# hackgt6-badge-prototype.net
KiCad netlist of a schematic drawn in EAGLE
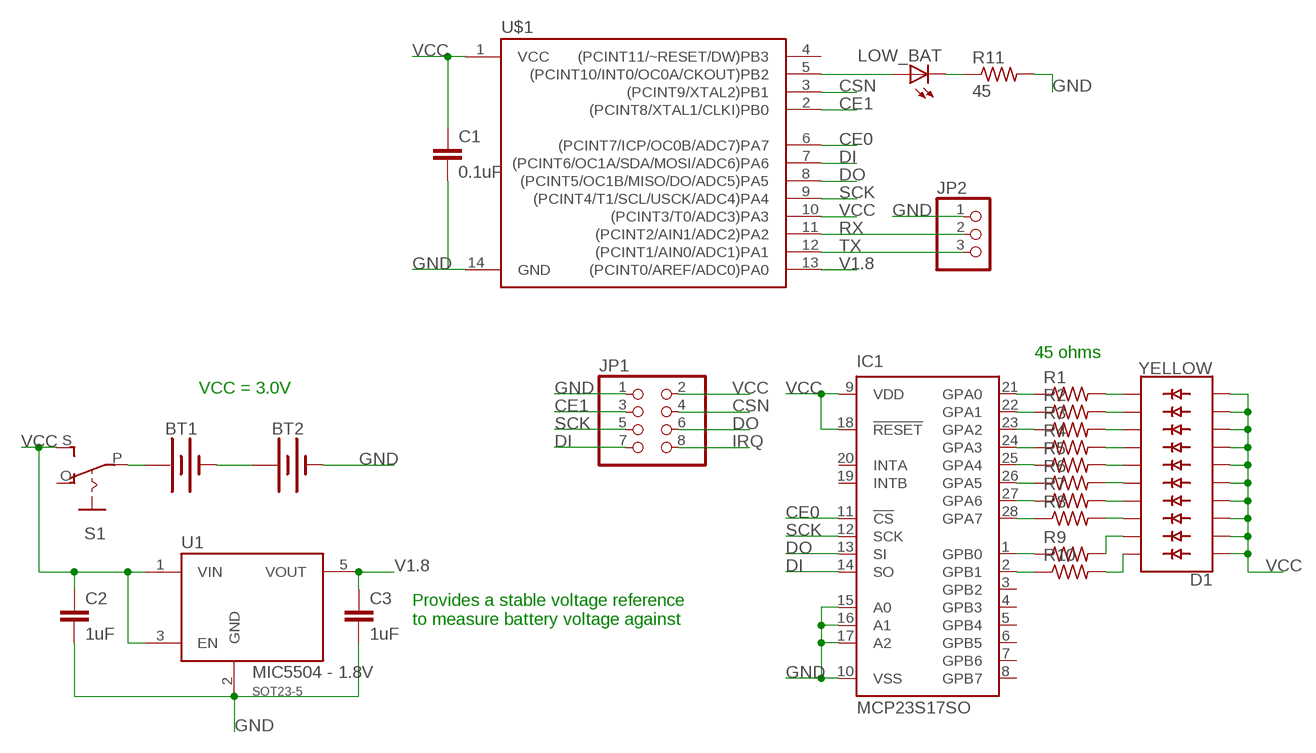
[diagram p0: schematic, sheet 1]

(export (version "E")
  (design (tool "Eeschema 10.0.6"))
  (components
    (comp (ref "BT1")
      (value "BATTERY-AA-SMD")
      (footprint "eagle-import:BATTERY-AA-SMD")
      (libsource (lib "eagle-import") (part "BATTERY-AA-SMD"))
    )
    (comp (ref "BT2")
      (value "BATTERY-AA-SMD")
      (footprint "eagle-import:BATTERY-AA-SMD")
      (libsource (lib "eagle-import") (part "BATTERY-AA-SMD"))
    )
    (comp (ref "C1")
      (value "0.1uF")
      (footprint "eagle-import:C1206")
      (libsource (lib "eagle-import") (part "C-EUC1206"))
    )
    (comp (ref "C2")
      (value "1uF")
      (footprint "eagle-import:C1206")
      (libsource (lib "eagle-import") (part "C-EUC1206"))
    )
    (comp (ref "C3")
      (value "1uF")
      (footprint "eagle-import:C1206")
      (libsource (lib "eagle-import") (part "C-EUC1206"))
    )
    (comp (ref "D1")
      (value "YELLOW")
      (footprint "eagle-import:LED_BARGRAPH_10")
      (libsource (lib "eagle-import") (part "LED_BARGRAPH_10YELLOW"))
    )
    (comp (ref "IC1")
      (value "MCP23S17SO")
      (footprint "eagle-import:SO28W")
      (fields (field (name "MF") "MICROCHIP") (field (name "MPN") "MCP23S17-E/SO"))
      (libsource (lib "eagle-import") (part "MCP23S17SO"))
    )
    (comp (ref "JP1")
      (value "PINHD-2X4/90")
      (footprint "eagle-import:2X04_90")
      (libsource (lib "eagle-import") (part "PINHD-2X4/90"))
    )
    (comp (ref "JP2")
      (value "PINHD-1X3")
      (footprint "eagle-import:1X03")
      (libsource (lib "eagle-import") (part "PINHD-1X3"))
    )
    (comp (ref "LOW_BAT")
      (value "LEDCHIPLED_1206")
      (footprint "eagle-import:CHIPLED_1206")
      (libsource (lib "eagle-import") (part "LEDCHIPLED_1206"))
    )
    (comp (ref "R1")
      (value "R-US_R1206")
      (footprint "eagle-import:R1206")
      (libsource (lib "eagle-import") (part "R-US_R1206"))
    )
    (comp (ref "R2")
      (value "R-US_R1206")
      (footprint "eagle-import:R1206")
      (libsource (lib "eagle-import") (part "R-US_R1206"))
    )
    (comp (ref "R3")
      (value "R-US_R1206")
      (footprint "eagle-import:R1206")
      (libsource (lib "eagle-import") (part "R-US_R1206"))
    )
    (comp (ref "R4")
      (value "R-US_R1206")
      (footprint "eagle-import:R1206")
      (libsource (lib "eagle-import") (part "R-US_R1206"))
    )
    (comp (ref "R5")
      (value "R-US_R1206")
      (footprint "eagle-import:R1206")
      (libsource (lib "eagle-import") (part "R-US_R1206"))
    )
    (comp (ref "R6")
      (value "R-US_R1206")
      (footprint "eagle-import:R1206")
      (libsource (lib "eagle-import") (part "R-US_R1206"))
    )
    (comp (ref "R7")
      (value "R-US_R1206")
      (footprint "eagle-import:R1206")
      (libsource (lib "eagle-import") (part "R-US_R1206"))
    )
    (comp (ref "R8")
      (value "R-US_R1206")
      (footprint "eagle-import:R1206")
      (libsource (lib "eagle-import") (part "R-US_R1206"))
    )
    (comp (ref "R9")
      (value "R-US_R1206")
      (footprint "eagle-import:R1206")
      (libsource (lib "eagle-import") (part "R-US_R1206"))
    )
    (comp (ref "R10")
      (value "R-US_R1206")
      (footprint "eagle-import:R1206")
      (libsource (lib "eagle-import") (part "R-US_R1206"))
    )
    (comp (ref "R11")
      (value "45")
      (footprint "eagle-import:R1206")
      (libsource (lib "eagle-import") (part "R-US_R1206"))
    )
    (comp (ref "S1")
      (value "EG1218S")
      (footprint "eagle-import:EG1218")
      (libsource (lib "eagle-import") (part "EG1218S"))
    )
    (comp (ref "U$1")
      (value "ATTINY84ATTINY84-20PU")
      (footprint "eagle-import:DIP14")
      (libsource (lib "eagle-import") (part "ATTINY84ATTINY84-20PU"))
    )
    (comp (ref "U1")
      (value "MIC5504 - 1.8V")
      (footprint "eagle-import:SOT23-5-DBV")
      (fields (field (name "PACKAGE") "SOT23-5"))
      (libsource (lib "eagle-import") (part "MIC550X-YM5"))
    )
  )
  (nets
    (net (code "1") (name "/CE0") (class "Default")
      (node (ref "IC1") (pin "11") (pinfunction "~{CS}_11") (pintype "input"))
      (node (ref "U$1") (pin "6") (pinfunction "(PCINT7/ICP/OC0B/ADC7)PA7_6") (pintype "bidirectional"))
    )
    (net (code "2") (name "/CE1") (class "Default")
      (node (ref "JP1") (pin "3") (pinfunction "3_3") (pintype "passive"))
      (node (ref "U$1") (pin "2") (pinfunction "(PCINT8/XTAL1/CLKI)PB0_2") (pintype "bidirectional"))
    )
    (net (code "3") (name "/CSN") (class "Default")
      (node (ref "JP1") (pin "4") (pinfunction "4_4") (pintype "passive"))
      (node (ref "U$1") (pin "3") (pinfunction "(PCINT9/XTAL2)PB1_3") (pintype "bidirectional"))
    )
    (net (code "4") (name "/DI") (class "Default")
      (node (ref "IC1") (pin "14") (pinfunction "SO_14") (pintype "output"))
      (node (ref "JP1") (pin "7") (pinfunction "7_7") (pintype "passive"))
      (node (ref "U$1") (pin "7") (pinfunction "(PCINT6/OC1A/SDA/MOSI/ADC6)PA6_7") (pintype "bidirectional"))
    )
    (net (code "5") (name "/DO") (class "Default")
      (node (ref "IC1") (pin "13") (pinfunction "SI_13") (pintype "input"))
      (node (ref "JP1") (pin "6") (pinfunction "6_6") (pintype "passive"))
      (node (ref "U$1") (pin "8") (pinfunction "(PCINT5/OC1B/MISO/DO/ADC5)PA5_8") (pintype "bidirectional"))
    )
    (net (code "6") (name "/GND") (class "Default")
      (node (ref "BT2") (pin "P$2") (pinfunction "-_P$2") (pintype "power_in"))
      (node (ref "BT2") (pin "P$4") (pinfunction "-_P$4") (pintype "power_in"))
      (node (ref "C1") (pin "2") (pinfunction "2_2") (pintype "passive"))
      (node (ref "C2") (pin "2") (pinfunction "2_2") (pintype "passive"))
      (node (ref "C3") (pin "2") (pinfunction "2_2") (pintype "passive"))
      (node (ref "IC1") (pin "10") (pinfunction "VSS_10") (pintype "power_in"))
      (node (ref "IC1") (pin "15") (pinfunction "A0_15") (pintype "input"))
      (node (ref "IC1") (pin "16") (pinfunction "A1_16") (pintype "input"))
      (node (ref "IC1") (pin "17") (pinfunction "A2_17") (pintype "input"))
      (node (ref "JP1") (pin "1") (pinfunction "1_1") (pintype "passive"))
      (node (ref "JP2") (pin "1") (pinfunction "1_1") (pintype "passive"))
      (node (ref "R11") (pin "2") (pinfunction "2_2") (pintype "passive"))
      (node (ref "U$1") (pin "14") (pinfunction "GND_14") (pintype "bidirectional"))
      (node (ref "U1") (pin "2") (pinfunction "GND_2") (pintype "bidirectional"))
    )
    (net (code "7") (name "/IRQ") (class "Default")
      (node (ref "JP1") (pin "8") (pinfunction "8_8") (pintype "passive"))
    )
    (net (code "8") (name "/RX") (class "Default")
      (node (ref "JP2") (pin "2") (pinfunction "2_2") (pintype "passive"))
      (node (ref "U$1") (pin "11") (pinfunction "(PCINT2/AIN1/ADC2)PA2_11") (pintype "bidirectional"))
    )
    (net (code "9") (name "/SCK") (class "Default")
      (node (ref "IC1") (pin "12") (pinfunction "SCK_12") (pintype "input"))
      (node (ref "JP1") (pin "5") (pinfunction "5_5") (pintype "passive"))
      (node (ref "U$1") (pin "9") (pinfunction "(PCINT4/T1/SCL/USCK/ADC4)PA4_9") (pintype "bidirectional"))
    )
    (net (code "10") (name "/TX") (class "Default")
      (node (ref "JP2") (pin "3") (pinfunction "3_3") (pintype "passive"))
      (node (ref "U$1") (pin "12") (pinfunction "(PCINT1/AIN0/ADC1)PA1_12") (pintype "bidirectional"))
    )
    (net (code "11") (name "/V1.8") (class "Default")
      (node (ref "C3") (pin "1") (pinfunction "1_1") (pintype "passive"))
      (node (ref "U$1") (pin "13") (pinfunction "(PCINT0/AREF/ADC0)PA0_13") (pintype "bidirectional"))
      (node (ref "U1") (pin "5") (pinfunction "VOUT_5") (pintype "bidirectional"))
    )
    (net (code "12") (name "/VCC") (class "Default")
      (node (ref "C1") (pin "1") (pinfunction "1_1") (pintype "passive"))
      (node (ref "C2") (pin "1") (pinfunction "1_1") (pintype "passive"))
      (node (ref "D1") (pin "1") (pinfunction "A_1") (pintype "passive"))
      (node (ref "D1") (pin "10") (pinfunction "A9_10") (pintype "passive"))
      (node (ref "D1") (pin "2") (pinfunction "A1_2") (pintype "passive"))
      (node (ref "D1") (pin "3") (pinfunction "A2_3") (pintype "passive"))
      (node (ref "D1") (pin "4") (pinfunction "A3_4") (pintype "passive"))
      (node (ref "D1") (pin "5") (pinfunction "A4_5") (pintype "passive"))
      (node (ref "D1") (pin "6") (pinfunction "A5_6") (pintype "passive"))
      (node (ref "D1") (pin "7") (pinfunction "A6_7") (pintype "passive"))
      (node (ref "D1") (pin "8") (pinfunction "A7_8") (pintype "passive"))
      (node (ref "D1") (pin "9") (pinfunction "A8_9") (pintype "passive"))
      (node (ref "IC1") (pin "18") (pinfunction "~{RESET}_18") (pintype "input"))
      (node (ref "IC1") (pin "9") (pinfunction "VDD_9") (pintype "power_in"))
      (node (ref "JP1") (pin "2") (pinfunction "2_2") (pintype "passive"))
      (node (ref "S1") (pin "S") (pinfunction "S_S") (pintype "passive"))
      (node (ref "U$1") (pin "1") (pinfunction "VCC_1") (pintype "bidirectional"))
      (node (ref "U$1") (pin "10") (pinfunction "(PCINT3/T0/ADC3)PA3_10") (pintype "bidirectional"))
      (node (ref "U1") (pin "1") (pinfunction "VIN_1") (pintype "bidirectional"))
      (node (ref "U1") (pin "3") (pinfunction "EN_3") (pintype "bidirectional"))
    )
    (net (code "13") (name "Net-(BT1-+-PadP$1)") (class "Default")
      (node (ref "BT1") (pin "P$1") (pinfunction "+_P$1") (pintype "power_in"))
      (node (ref "BT1") (pin "P$3") (pinfunction "+_P$3") (pintype "power_in"))
      (node (ref "S1") (pin "P") (pinfunction "P_P") (pintype "passive"))
    )
    (net (code "14") (name "Net-(BT1---PadP$2)") (class "Default")
      (node (ref "BT1") (pin "P$2") (pinfunction "-_P$2") (pintype "power_in"))
      (node (ref "BT1") (pin "P$4") (pinfunction "-_P$4") (pintype "power_in"))
      (node (ref "BT2") (pin "P$1") (pinfunction "+_P$1") (pintype "power_in"))
      (node (ref "BT2") (pin "P$3") (pinfunction "+_P$3") (pintype "power_in"))
    )
    (net (code "15") (name "Net-(D1-C)") (class "Default")
      (node (ref "D1") (pin "20") (pinfunction "C_20") (pintype "passive"))
      (node (ref "R10") (pin "2") (pinfunction "2_2") (pintype "passive"))
    )
    (net (code "16") (name "Net-(D1-C1)") (class "Default")
      (node (ref "D1") (pin "19") (pinfunction "C1_19") (pintype "passive"))
      (node (ref "R9") (pin "2") (pinfunction "2_2") (pintype "passive"))
    )
    (net (code "17") (name "Net-(D1-C2)") (class "Default")
      (node (ref "D1") (pin "18") (pinfunction "C2_18") (pintype "passive"))
      (node (ref "R8") (pin "2") (pinfunction "2_2") (pintype "passive"))
    )
    (net (code "18") (name "Net-(D1-C3)") (class "Default")
      (node (ref "D1") (pin "17") (pinfunction "C3_17") (pintype "passive"))
      (node (ref "R7") (pin "2") (pinfunction "2_2") (pintype "passive"))
    )
    (net (code "19") (name "Net-(D1-C4)") (class "Default")
      (node (ref "D1") (pin "16") (pinfunction "C4_16") (pintype "passive"))
      (node (ref "R6") (pin "2") (pinfunction "2_2") (pintype "passive"))
    )
    (net (code "20") (name "Net-(D1-C5)") (class "Default")
      (node (ref "D1") (pin "15") (pinfunction "C5_15") (pintype "passive"))
      (node (ref "R5") (pin "2") (pinfunction "2_2") (pintype "passive"))
    )
    (net (code "21") (name "Net-(D1-C6)") (class "Default")
      (node (ref "D1") (pin "14") (pinfunction "C6_14") (pintype "passive"))
      (node (ref "R4") (pin "2") (pinfunction "2_2") (pintype "passive"))
    )
    (net (code "22") (name "Net-(D1-C7)") (class "Default")
      (node (ref "D1") (pin "13") (pinfunction "C7_13") (pintype "passive"))
      (node (ref "R3") (pin "2") (pinfunction "2_2") (pintype "passive"))
    )
    (net (code "23") (name "Net-(D1-C8)") (class "Default")
      (node (ref "D1") (pin "12") (pinfunction "C8_12") (pintype "passive"))
      (node (ref "R2") (pin "2") (pinfunction "2_2") (pintype "passive"))
    )
    (net (code "24") (name "Net-(D1-C9)") (class "Default")
      (node (ref "D1") (pin "11") (pinfunction "C9_11") (pintype "passive"))
      (node (ref "R1") (pin "2") (pinfunction "2_2") (pintype "passive"))
    )
    (net (code "25") (name "Net-(IC1-GPA0)") (class "Default")
      (node (ref "IC1") (pin "21") (pinfunction "GPA0_21") (pintype "bidirectional"))
      (node (ref "R1") (pin "1") (pinfunction "1_1") (pintype "passive"))
    )
    (net (code "26") (name "Net-(IC1-GPA1)") (class "Default")
      (node (ref "IC1") (pin "22") (pinfunction "GPA1_22") (pintype "bidirectional"))
      (node (ref "R2") (pin "1") (pinfunction "1_1") (pintype "passive"))
    )
    (net (code "27") (name "Net-(IC1-GPA2)") (class "Default")
      (node (ref "IC1") (pin "23") (pinfunction "GPA2_23") (pintype "bidirectional"))
      (node (ref "R3") (pin "1") (pinfunction "1_1") (pintype "passive"))
    )
    (net (code "28") (name "Net-(IC1-GPA3)") (class "Default")
      (node (ref "IC1") (pin "24") (pinfunction "GPA3_24") (pintype "bidirectional"))
      (node (ref "R4") (pin "1") (pinfunction "1_1") (pintype "passive"))
    )
    (net (code "29") (name "Net-(IC1-GPA4)") (class "Default")
      (node (ref "IC1") (pin "25") (pinfunction "GPA4_25") (pintype "bidirectional"))
      (node (ref "R5") (pin "1") (pinfunction "1_1") (pintype "passive"))
    )
    (net (code "30") (name "Net-(IC1-GPA5)") (class "Default")
      (node (ref "IC1") (pin "26") (pinfunction "GPA5_26") (pintype "bidirectional"))
      (node (ref "R6") (pin "1") (pinfunction "1_1") (pintype "passive"))
    )
    (net (code "31") (name "Net-(IC1-GPA6)") (class "Default")
      (node (ref "IC1") (pin "27") (pinfunction "GPA6_27") (pintype "bidirectional"))
      (node (ref "R7") (pin "1") (pinfunction "1_1") (pintype "passive"))
    )
    (net (code "32") (name "Net-(IC1-GPA7)") (class "Default")
      (node (ref "IC1") (pin "28") (pinfunction "GPA7_28") (pintype "bidirectional"))
      (node (ref "R8") (pin "1") (pinfunction "1_1") (pintype "passive"))
    )
    (net (code "33") (name "Net-(IC1-GPB0)") (class "Default")
      (node (ref "IC1") (pin "1") (pinfunction "GPB0_1") (pintype "bidirectional"))
      (node (ref "R9") (pin "1") (pinfunction "1_1") (pintype "passive"))
    )
    (net (code "34") (name "Net-(IC1-GPB1)") (class "Default")
      (node (ref "IC1") (pin "2") (pinfunction "GPB1_2") (pintype "bidirectional"))
      (node (ref "R10") (pin "1") (pinfunction "1_1") (pintype "passive"))
    )
    (net (code "35") (name "Net-(LOW_BAT-PadC)") (class "Default")
      (node (ref "LOW_BAT") (pin "C") (pinfunction "C_C") (pintype "passive"))
      (node (ref "R11") (pin "1") (pinfunction "1_1") (pintype "passive"))
    )
    (net (code "36") (name "Net-(U$1-(PCINT10{slash}INT0{slash}OC0A{slash}CKOUT)PB2)") (class "Default")
      (node (ref "LOW_BAT") (pin "A") (pinfunction "A_A") (pintype "passive"))
      (node (ref "U$1") (pin "5") (pinfunction "(PCINT10/INT0/OC0A/CKOUT)PB2_5") (pintype "bidirectional"))
    )
    (net (code "37") (name "unconnected-(IC1-GPB2-Pad3)") (class "Default")
      (node (ref "IC1") (pin "3") (pinfunction "GPB2_3") (pintype "bidirectional"))
    )
    (net (code "38") (name "unconnected-(IC1-GPB3-Pad4)") (class "Default")
      (node (ref "IC1") (pin "4") (pinfunction "GPB3_4") (pintype "bidirectional"))
    )
    (net (code "39") (name "unconnected-(IC1-GPB4-Pad5)") (class "Default")
      (node (ref "IC1") (pin "5") (pinfunction "GPB4_5") (pintype "bidirectional"))
    )
    (net (code "40") (name "unconnected-(IC1-GPB5-Pad6)") (class "Default")
      (node (ref "IC1") (pin "6") (pinfunction "GPB5_6") (pintype "bidirectional"))
    )
    (net (code "41") (name "unconnected-(IC1-GPB6-Pad7)") (class "Default")
      (node (ref "IC1") (pin "7") (pinfunction "GPB6_7") (pintype "bidirectional"))
    )
    (net (code "42") (name "unconnected-(IC1-GPB7-Pad8)") (class "Default")
      (node (ref "IC1") (pin "8") (pinfunction "GPB7_8") (pintype "bidirectional"))
    )
    (net (code "43") (name "unconnected-(IC1-INTA-Pad20)") (class "Default")
      (node (ref "IC1") (pin "20") (pinfunction "INTA_20") (pintype "output"))
    )
    (net (code "44") (name "unconnected-(IC1-INTB-Pad19)") (class "Default")
      (node (ref "IC1") (pin "19") (pinfunction "INTB_19") (pintype "output"))
    )
    (net (code "45") (name "unconnected-(S1-PadO)") (class "Default")
      (node (ref "S1") (pin "O") (pinfunction "O_O") (pintype "passive"))
    )
    (net (code "46") (name "unconnected-(U$1-(PCINT11{slash}~{RESET{slash}DW})PB3-Pad4)") (class "Default")
      (node (ref "U$1") (pin "4") (pinfunction "(PCINT11/~{RESET/DW})PB3_4") (pintype "bidirectional"))
    )
  )
)
